# display.net
KiCad netlist of a schematic drawn in Altium Designer
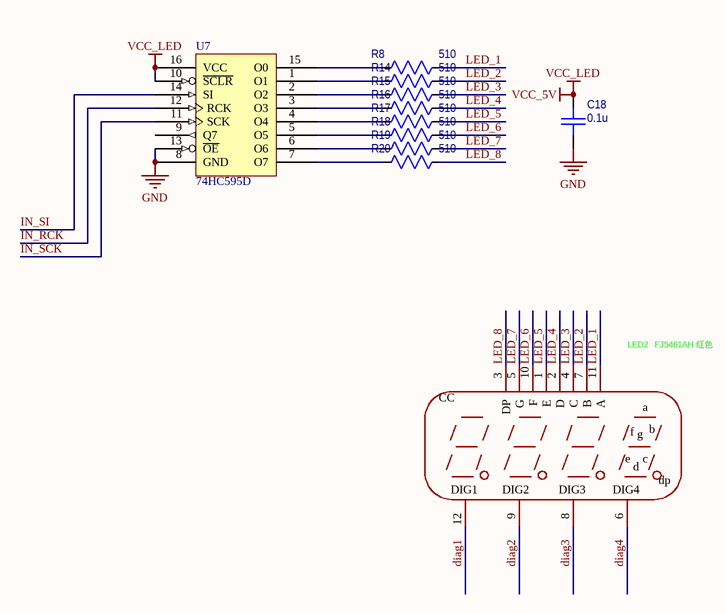
[diagram p0: display.SchDoc]

(export (version "E")
  (design (tool "Eeschema 10.0.6"))
  (components
    (comp (ref "C18")
      (value "0.1u")
      (footprint "CAPC1608X092N_0603")
      (description "Capacitor, MLCC")
      (fields (field (name "MANUFACTURER") "KEMET") (field (name "PARTNUMBER") "C0603C104M5RACTU"))
      (libsource (lib "Karl") (part "Capacitor_0603"))
    )
    (comp (ref "LED2")
      (value "FJ5461AH 红色")
      (footprint "LED-SEG-TH_12P-L30.0-W14.0-P2.54-S10.26-BL:LED-SEG-TH_12P-L30.0-W14.0-P2.54-S10.26-BL")
      (fields (field (name "MANUFACTURER") "志浩"))
      (libsource (lib "altium-import") (part "root_0_FJ5461AH 红色_"))
    )
    (comp (ref "R8")
      (value "510")
      (footprint "RESC1608X055N_0603")
      (description "Resistor, Standard")
      (fields (field (name "MANUFACTURER") "Yageo") (field (name "PARTNUMBER") "RC0603FR-1075KL"))
      (libsource (lib "Karl") (part "Resistor_0603"))
    )
    (comp (ref "R14")
      (value "510")
      (footprint "RESC1608X055N_0603")
      (description "Resistor, Standard")
      (fields (field (name "MANUFACTURER") "Yageo") (field (name "PARTNUMBER") "RC0603FR-1075KL"))
      (libsource (lib "Karl") (part "Resistor_0603"))
    )
    (comp (ref "R15")
      (value "510")
      (footprint "RESC1608X055N_0603")
      (description "Resistor, Standard")
      (fields (field (name "MANUFACTURER") "Yageo") (field (name "PARTNUMBER") "RC0603FR-1075KL"))
      (libsource (lib "Karl") (part "Resistor_0603"))
    )
    (comp (ref "R16")
      (value "510")
      (footprint "RESC1608X055N_0603")
      (description "Resistor, Standard")
      (fields (field (name "MANUFACTURER") "Yageo") (field (name "PARTNUMBER") "RC0603FR-1075KL"))
      (libsource (lib "Karl") (part "Resistor_0603"))
    )
    (comp (ref "R17")
      (value "510")
      (footprint "RESC1608X055N_0603")
      (description "Resistor, Standard")
      (fields (field (name "MANUFACTURER") "Yageo") (field (name "PARTNUMBER") "RC0603FR-1075KL"))
      (libsource (lib "Karl") (part "Resistor_0603"))
    )
    (comp (ref "R18")
      (value "510")
      (footprint "RESC1608X055N_0603")
      (description "Resistor, Standard")
      (fields (field (name "MANUFACTURER") "Yageo") (field (name "PARTNUMBER") "RC0603FR-1075KL"))
      (libsource (lib "Karl") (part "Resistor_0603"))
    )
    (comp (ref "R19")
      (value "510")
      (footprint "RESC1608X055N_0603")
      (description "Resistor, Standard")
      (fields (field (name "MANUFACTURER") "Yageo") (field (name "PARTNUMBER") "RC0603FR-1075KL"))
      (libsource (lib "Karl") (part "Resistor_0603"))
    )
    (comp (ref "R20")
      (value "510")
      (footprint "RESC1608X055N_0603")
      (description "Resistor, Standard")
      (fields (field (name "MANUFACTURER") "Yageo") (field (name "PARTNUMBER") "RC0603FR-1075KL"))
      (libsource (lib "Karl") (part "Resistor_0603"))
    )
    (comp (ref "U7")
      (value "74HC595D")
      (footprint "SOIC-16_L9.9-W3.9-P1.27-LS6.0-BL:SOIC-16_L9.9-W3.9-P1.27-LS6.0-BL")
      (libsource (lib "DI16") (part "74HC595"))
    )
  )
  (nets
    (net (code "1") (name "/IN_RCK") (class "Default")
      (node (ref "U7") (pin "12") (pinfunction "RCK_12") (pintype "input"))
    )
    (net (code "2") (name "/IN_SCK") (class "Default")
      (node (ref "U7") (pin "11") (pinfunction "SCK_11") (pintype "input"))
    )
    (net (code "3") (name "/IN_SI") (class "Default")
      (node (ref "U7") (pin "14") (pinfunction "SI_14") (pintype "input"))
    )
    (net (code "4") (name "/LED_1") (class "Default")
      (node (ref "LED2") (pin "11") (pinfunction "A_11") (pintype "passive"))
      (node (ref "R8") (pin "1") (pinfunction "1_1") (pintype "passive"))
    )
    (net (code "5") (name "/LED_2") (class "Default")
      (node (ref "LED2") (pin "7") (pinfunction "B_7") (pintype "passive"))
      (node (ref "R14") (pin "1") (pinfunction "1_1") (pintype "passive"))
    )
    (net (code "6") (name "/LED_3") (class "Default")
      (node (ref "LED2") (pin "4") (pinfunction "C_4") (pintype "passive"))
      (node (ref "R15") (pin "1") (pinfunction "1_1") (pintype "passive"))
    )
    (net (code "7") (name "/LED_4") (class "Default")
      (node (ref "LED2") (pin "2") (pinfunction "D_2") (pintype "passive"))
      (node (ref "R16") (pin "1") (pinfunction "1_1") (pintype "passive"))
    )
    (net (code "8") (name "/LED_5") (class "Default")
      (node (ref "LED2") (pin "1") (pinfunction "E_1") (pintype "passive"))
      (node (ref "R17") (pin "1") (pinfunction "1_1") (pintype "passive"))
    )
    (net (code "9") (name "/LED_6") (class "Default")
      (node (ref "LED2") (pin "10") (pinfunction "F_10") (pintype "passive"))
      (node (ref "R18") (pin "1") (pinfunction "1_1") (pintype "passive"))
    )
    (net (code "10") (name "/LED_7") (class "Default")
      (node (ref "LED2") (pin "5") (pinfunction "G_5") (pintype "passive"))
      (node (ref "R19") (pin "1") (pinfunction "1_1") (pintype "passive"))
    )
    (net (code "11") (name "/LED_8") (class "Default")
      (node (ref "LED2") (pin "3") (pinfunction "DP_3") (pintype "passive"))
      (node (ref "R20") (pin "1") (pinfunction "1_1") (pintype "passive"))
    )
    (net (code "12") (name "/diag1") (class "Default")
      (node (ref "LED2") (pin "12") (pinfunction "DIG1_12") (pintype "passive"))
    )
    (net (code "13") (name "/diag2") (class "Default")
      (node (ref "LED2") (pin "9") (pinfunction "DIG2_9") (pintype "passive"))
    )
    (net (code "14") (name "/diag3") (class "Default")
      (node (ref "LED2") (pin "8") (pinfunction "DIG3_8") (pintype "passive"))
    )
    (net (code "15") (name "/diag4") (class "Default")
      (node (ref "LED2") (pin "6") (pinfunction "DIG4_6") (pintype "passive"))
    )
    (net (code "16") (name "GND") (class "Default")
      (node (ref "C18") (pin "2") (pinfunction "2_2") (pintype "passive"))
      (node (ref "U7") (pin "13") (pinfunction "~{OE}_13") (pintype "input"))
      (node (ref "U7") (pin "8") (pinfunction "GND_8") (pintype "power_in"))
    )
    (net (code "17") (name "Net-(U7-O0)") (class "Default")
      (node (ref "R8") (pin "2") (pinfunction "2_2") (pintype "passive"))
      (node (ref "U7") (pin "15") (pinfunction "O0_15") (pintype "tri_state"))
    )
    (net (code "18") (name "Net-(U7-O1)") (class "Default")
      (node (ref "R14") (pin "2") (pinfunction "2_2") (pintype "passive"))
      (node (ref "U7") (pin "1") (pinfunction "O1_1") (pintype "tri_state"))
    )
    (net (code "19") (name "Net-(U7-O2)") (class "Default")
      (node (ref "R15") (pin "2") (pinfunction "2_2") (pintype "passive"))
      (node (ref "U7") (pin "2") (pinfunction "O2_2") (pintype "tri_state"))
    )
    (net (code "20") (name "Net-(U7-O3)") (class "Default")
      (node (ref "R16") (pin "2") (pinfunction "2_2") (pintype "passive"))
      (node (ref "U7") (pin "3") (pinfunction "O3_3") (pintype "tri_state"))
    )
    (net (code "21") (name "Net-(U7-O4)") (class "Default")
      (node (ref "R17") (pin "2") (pinfunction "2_2") (pintype "passive"))
      (node (ref "U7") (pin "4") (pinfunction "O4_4") (pintype "tri_state"))
    )
    (net (code "22") (name "Net-(U7-O5)") (class "Default")
      (node (ref "R18") (pin "2") (pinfunction "2_2") (pintype "passive"))
      (node (ref "U7") (pin "5") (pinfunction "O5_5") (pintype "tri_state"))
    )
    (net (code "23") (name "Net-(U7-O6)") (class "Default")
      (node (ref "R19") (pin "2") (pinfunction "2_2") (pintype "passive"))
      (node (ref "U7") (pin "6") (pinfunction "O6_6") (pintype "tri_state"))
    )
    (net (code "24") (name "Net-(U7-O7)") (class "Default")
      (node (ref "R20") (pin "2") (pinfunction "2_2") (pintype "passive"))
      (node (ref "U7") (pin "7") (pinfunction "O7_7") (pintype "tri_state"))
    )
    (net (code "25") (name "VCC_5V") (class "Default")
      (node (ref "C18") (pin "1") (pinfunction "1_1") (pintype "passive"))
      (node (ref "U7") (pin "10") (pinfunction "~{SCLR}_10") (pintype "input"))
      (node (ref "U7") (pin "16") (pinfunction "VCC_16") (pintype "power_in"))
    )
    (net (code "26") (name "unconnected-(U7-Q7-Pad9)") (class "Default")
      (node (ref "U7") (pin "9") (pinfunction "Q7_9") (pintype "output"))
    )
  )
)
